# esp32_pico.net
KiCad netlist of a schematic drawn in Altium Designer
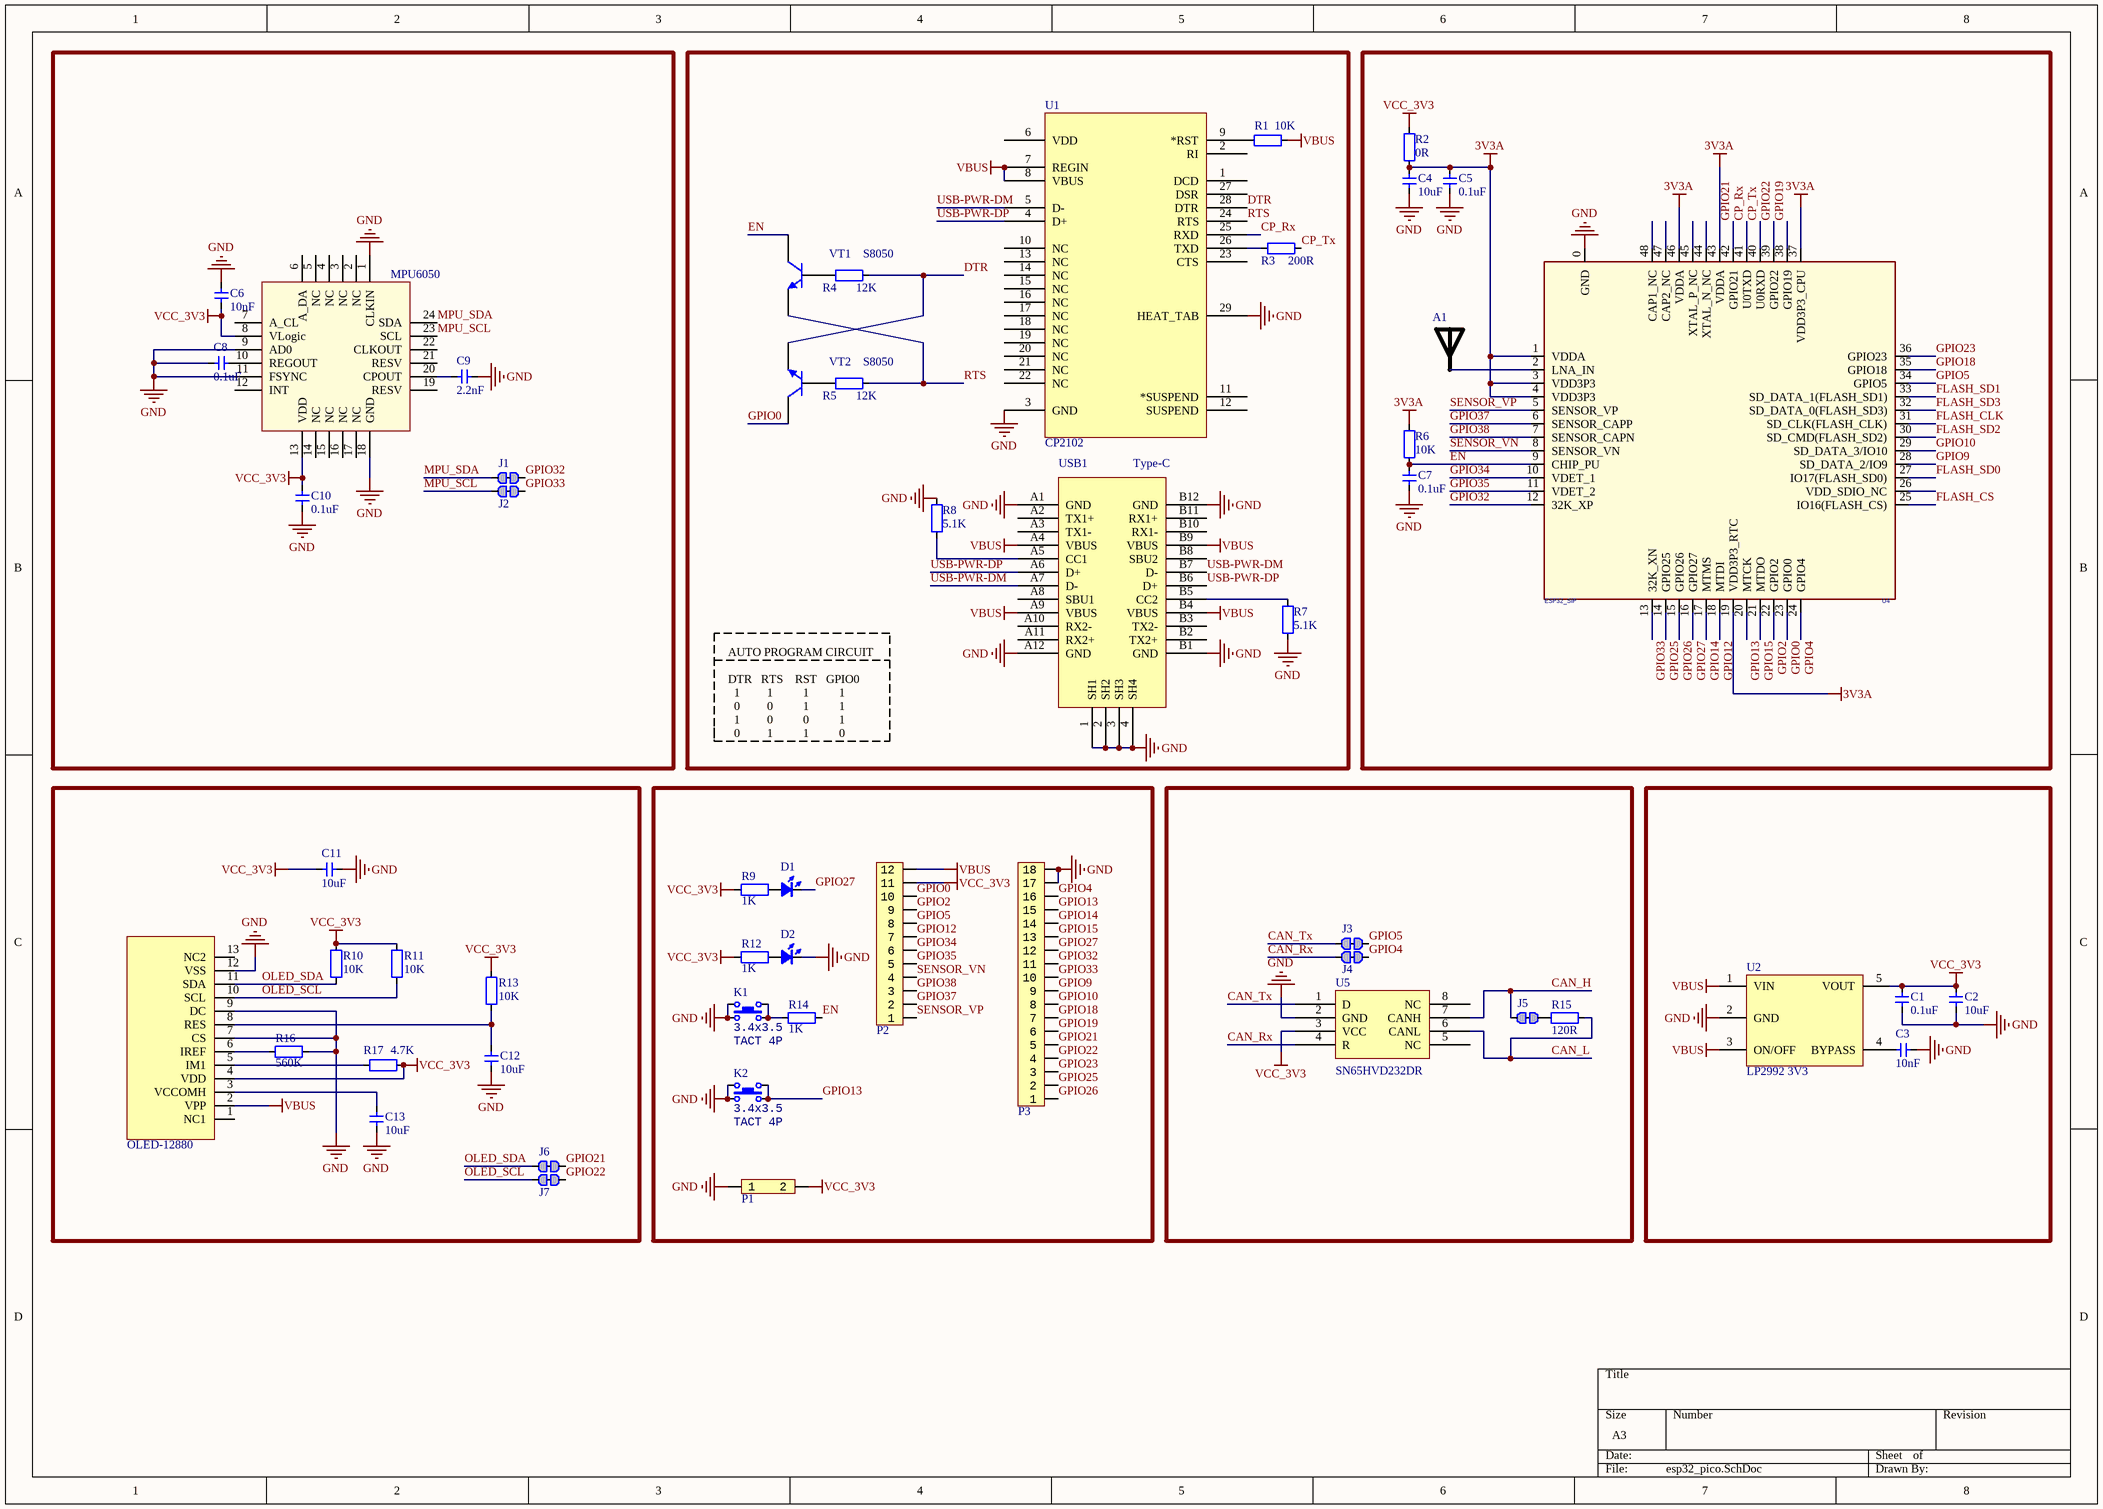
[diagram p0: esp32_pico.SchDoc]

(export (version "E")
  (design (tool "Eeschema 10.0.6"))
  (components
    (comp (ref "1")
      (value "OLED-12880")
      (footprint "OLED-12880")
      (libsource (lib "mLib") (part "OLED-12880"))
    )
    (comp (ref "A1")
      (value "RAINSUN")
      (footprint "ANT-Rainsun-AN5120")
      (libsource (lib "MyPcbLib") (part "ANT-Rainsun-AP5120"))
    )
    (comp (ref "C1")
      (value "0.1uF")
      (footprint "CAP_0402")
      (description "Capacitor")
      (libsource (lib "MyPcbLib") (part "电容-0402"))
    )
    (comp (ref "C2")
      (value "10uF")
      (footprint "CAP_0402")
      (description "Capacitor")
      (libsource (lib "MyPcbLib") (part "电容-0402"))
    )
    (comp (ref "C3")
      (value "10nF")
      (footprint "CAP_0402")
      (description "Capacitor")
      (libsource (lib "MyPcbLib") (part "电容-0402"))
    )
    (comp (ref "C4")
      (value "10uF")
      (footprint "CAP_0402")
      (description "Capacitor")
      (libsource (lib "MyPcbLib") (part "电容-0402"))
    )
    (comp (ref "C5")
      (value "0.1uF")
      (footprint "CAP_0402")
      (description "Capacitor")
      (libsource (lib "MyPcbLib") (part "电容-0402"))
    )
    (comp (ref "C6")
      (value "10nF")
      (footprint "CAP_0402")
      (description "Capacitor")
      (libsource (lib "MyPcbLib") (part "电容-0402"))
    )
    (comp (ref "C7")
      (value "0.1uF")
      (footprint "CAP_0402")
      (description "Capacitor")
      (libsource (lib "MyPcbLib") (part "电容-0402"))
    )
    (comp (ref "C8")
      (value "0.1uF")
      (footprint "CAP_0402")
      (description "Capacitor")
      (libsource (lib "MyPcbLib") (part "电容-0402"))
    )
    (comp (ref "C9")
      (value "2.2nF")
      (footprint "CAP_0402")
      (description "Capacitor")
      (libsource (lib "MyPcbLib") (part "电容-0402"))
    )
    (comp (ref "C10")
      (value "0.1uF")
      (footprint "CAP_0402")
      (description "Capacitor")
      (libsource (lib "MyPcbLib") (part "电容-0402"))
    )
    (comp (ref "C11")
      (value "10uF")
      (footprint "CAP_0402")
      (description "Capacitor")
      (libsource (lib "MyPcbLib") (part "电容-0402"))
    )
    (comp (ref "C12")
      (value "10uF")
      (footprint "CAP_0402")
      (description "Capacitor")
      (libsource (lib "MyPcbLib") (part "电容-0402"))
    )
    (comp (ref "C13")
      (value "10uF")
      (footprint "CAP_0402")
      (description "Capacitor")
      (libsource (lib "MyPcbLib") (part "电容-0402"))
    )
    (comp (ref "D1")
      (value "color?")
      (footprint "LED_0402_RED")
      (description "LED")
      (libsource (lib "KitSprout") (part "LED_0402"))
    )
    (comp (ref "D2")
      (value "color?")
      (footprint "LED_0402_RED")
      (description "LED")
      (libsource (lib "KitSprout") (part "LED_0402"))
    )
    (comp (ref "J1")
      (value "跳线")
      (footprint "0402-0R")
      (description "Resistor")
      (fields (field (name "PUBLISHER") "Altium Limited"))
      (libsource (lib "MyPcbLib") (part "跳线"))
    )
    (comp (ref "J2")
      (value "跳线")
      (footprint "0402-0R")
      (description "Resistor")
      (fields (field (name "PUBLISHER") "Altium Limited"))
      (libsource (lib "MyPcbLib") (part "跳线"))
    )
    (comp (ref "J3")
      (value "跳线")
      (footprint "0402-0R")
      (description "Resistor")
      (fields (field (name "PUBLISHER") "Altium Limited"))
      (libsource (lib "MyPcbLib") (part "跳线"))
    )
    (comp (ref "J4")
      (value "跳线")
      (footprint "0402-0R")
      (description "Resistor")
      (fields (field (name "PUBLISHER") "Altium Limited"))
      (libsource (lib "MyPcbLib") (part "跳线"))
    )
    (comp (ref "J5")
      (value "跳线")
      (footprint "0402-0R")
      (description "Resistor")
      (fields (field (name "PUBLISHER") "Altium Limited"))
      (libsource (lib "MyPcbLib") (part "跳线"))
    )
    (comp (ref "J6")
      (value "跳线")
      (footprint "0402-0R")
      (description "Resistor")
      (fields (field (name "PUBLISHER") "Altium Limited"))
      (libsource (lib "MyPcbLib") (part "跳线"))
    )
    (comp (ref "J7")
      (value "跳线")
      (footprint "0402-0R")
      (description "Resistor")
      (fields (field (name "PUBLISHER") "Altium Limited"))
      (libsource (lib "MyPcbLib") (part "跳线"))
    )
    (comp (ref "K1")
      (value "3.4x3.5")
      (footprint "ButtonTACT_3.5*3.55_90")
      (description "Button")
      (fields (field (name "TYPE") "TACT 4P") (field (name "Comment") "TACT 4P"))
      (libsource (lib "KitSprout") (part "ButtonTACT"))
    )
    (comp (ref "K2")
      (value "3.4x3.5")
      (footprint "ButtonTACT_3.5*3.55_90")
      (description "Button")
      (fields (field (name "TYPE") "TACT 4P") (field (name "Comment") "TACT 4P"))
      (libsource (lib "KitSprout") (part "ButtonTACT"))
    )
    (comp (ref "P1")
      (value "HDR2x1_2.54")
      (footprint "HDR1X2_2.54_180")
      (description "Header")
      (libsource (lib "KitSprout") (part "HDR2x1_2.54"))
    )
    (comp (ref "P2")
      (value "HDR1x12_2.54")
      (footprint "HDR1X12_2.54_180")
      (description "Header")
      (libsource (lib "KitSprout") (part "HDR1x12_2.54"))
    )
    (comp (ref "P3")
      (value "HDR1x18_2.54")
      (footprint "HDR1X18_2.54_180")
      (description "Header")
      (libsource (lib "KitSprout") (part "HDR1x18_2.54"))
    )
    (comp (ref "R1")
      (value "10K")
      (footprint "RES_0402")
      (description "Resistor")
      (libsource (lib "") (part "电阻-0402_3"))
    )
    (comp (ref "R2")
      (value "0R")
      (footprint "RES_0402")
      (description "Resistor")
      (libsource (lib "") (part "电阻-0402_1"))
    )
    (comp (ref "R3")
      (value "200R")
      (footprint "RES_0402")
      (description "Resistor")
      (libsource (lib "") (part "电阻-0402_3"))
    )
    (comp (ref "R4")
      (value "12K")
      (footprint "RES_0402")
      (description "Resistor")
      (libsource (lib "") (part "电阻-0402_3"))
    )
    (comp (ref "R5")
      (value "12K")
      (footprint "RES_0402")
      (description "Resistor")
      (libsource (lib "") (part "电阻-0402_3"))
    )
    (comp (ref "R6")
      (value "10K")
      (footprint "RES_0402")
      (description "Resistor")
      (libsource (lib "") (part "电阻-0402_1"))
    )
    (comp (ref "R7")
      (value "5.1K")
      (footprint "RES_0402")
      (description "Resistor")
      (libsource (lib "") (part "电阻-0402_1"))
    )
    (comp (ref "R8")
      (value "5.1K")
      (footprint "RES_0402")
      (description "Resistor")
      (libsource (lib "") (part "电阻-0402_2"))
    )
    (comp (ref "R9")
      (value "1K")
      (footprint "RES_0402")
      (description "Resistor")
      (libsource (lib "MyPcbLib") (part "电阻-0402"))
    )
    (comp (ref "R10")
      (value "10K")
      (footprint "RES_0402")
      (description "Resistor")
      (libsource (lib "") (part "电阻-0402_2"))
    )
    (comp (ref "R11")
      (value "10K")
      (footprint "RES_0402")
      (description "Resistor")
      (libsource (lib "") (part "电阻-0402_2"))
    )
    (comp (ref "R12")
      (value "1K")
      (footprint "RES_0402")
      (description "Resistor")
      (libsource (lib "MyPcbLib") (part "电阻-0402"))
    )
    (comp (ref "R13")
      (value "10K")
      (footprint "RES_0402")
      (description "Resistor")
      (libsource (lib "") (part "电阻-0402_2"))
    )
    (comp (ref "R14")
      (value "1K")
      (footprint "RES_0402")
      (description "Resistor")
      (libsource (lib "MyPcbLib") (part "电阻-0402"))
    )
    (comp (ref "R15")
      (value "120R")
      (footprint "RES_0402")
      (description "Resistor")
      (libsource (lib "MyPcbLib") (part "电阻-0402"))
    )
    (comp (ref "R16")
      (value "560K")
      (footprint "RES_0402")
      (description "Resistor")
      (libsource (lib "MyPcbLib") (part "电阻-0402"))
    )
    (comp (ref "R17")
      (value "4.7K")
      (footprint "RES_0402")
      (description "Resistor")
      (libsource (lib "MyPcbLib") (part "电阻-0402"))
    )
    (comp (ref "U1")
      (value "CP2102")
      (footprint "QFN-28")
      (description "USB转TTL")
      (libsource (lib "mLib") (part "CP2102"))
    )
    (comp (ref "U2")
      (value "LP2992 3V3")
      (footprint "SOT23-5")
      (description "LDO")
      (libsource (lib "MyPcbLib") (part "LP2992"))
    )
    (comp (ref "U3")
      (value "MPU6050")
      (footprint "QFN-24")
      (description "六轴传感器")
      (libsource (lib "mLib") (part "MPU6050"))
    )
    (comp (ref "U4")
      (value "ESP32_SIP")
      (footprint "QFN-48_7X7")
      (libsource (lib "MyPcbLib") (part "ESP32-PICO"))
    )
    (comp (ref "U5")
      (value "SN65HVD232D")
      (footprint "SO-8")
      (fields
        (field (name "MANUFACTURER") "Texas Instruments")
        (field (name "MANUFACTURER PART NUMBER") "SN65HVD232DR")
      )
      (libsource (lib "MyPcbLib") (part "SN65HVD232D"))
    )
    (comp (ref "USB1")
      (value "Type-C")
      (footprint "Type-C-TOP")
      (libsource (lib "MyPcbLib") (part "USB-Type-C-TOP"))
    )
    (comp (ref "VT1")
      (value "S8050")
      (footprint "SMT_TRIODE_NPN")
      (description "Surface mount NPN transistor, package SOT-23")
      (libsource (lib "MyPcbLib") (part "SMT_TRIODE_NPN"))
    )
    (comp (ref "VT2")
      (value "S8050")
      (footprint "SMT_TRIODE_NPN")
      (description "Surface mount NPN transistor, package SOT-23")
      (libsource (lib "MyPcbLib") (part "SMT_TRIODE_NPN"))
    )
  )
  (nets
    (net (code "1") (name "/CAN_H") (class "Default")
      (node (ref "J5") (pin "1") (pinfunction "1_1") (pintype "passive"))
      (node (ref "U5") (pin "7") (pinfunction "CANH_7") (pintype "passive"))
    )
    (net (code "2") (name "/CAN_L") (class "Default")
      (node (ref "R15") (pin "2") (pinfunction "2_2") (pintype "passive"))
      (node (ref "U5") (pin "6") (pinfunction "CANL_6") (pintype "passive"))
    )
    (net (code "3") (name "/CAN_Rx") (class "Default")
      (node (ref "J4") (pin "1") (pinfunction "1_1") (pintype "passive"))
      (node (ref "U5") (pin "4") (pinfunction "R_4") (pintype "passive"))
    )
    (net (code "4") (name "/CAN_Tx") (class "Default")
      (node (ref "J3") (pin "1") (pinfunction "1_1") (pintype "passive"))
      (node (ref "U5") (pin "1") (pinfunction "D_1") (pintype "passive"))
    )
    (net (code "5") (name "/CP_Rx") (class "Default")
      (node (ref "U1") (pin "25") (pinfunction "RXD_25") (pintype "passive"))
      (node (ref "U4") (pin "41") (pinfunction "U0TXD_41") (pintype "power_in"))
    )
    (net (code "6") (name "/CP_Tx") (class "Default")
      (node (ref "R3") (pin "1") (pinfunction "1_1") (pintype "passive"))
      (node (ref "U4") (pin "40") (pinfunction "U0RXD_40") (pintype "power_in"))
    )
    (net (code "7") (name "/DTR") (class "Default")
      (node (ref "R4") (pin "1") (pinfunction "1_1") (pintype "passive"))
      (node (ref "U1") (pin "28") (pinfunction "DTR_28") (pintype "passive"))
      (node (ref "VT2") (pin "2") (pinfunction "E_2") (pintype "passive"))
    )
    (net (code "8") (name "/EN") (class "Default")
      (node (ref "C7") (pin "1") (pinfunction "1_1") (pintype "passive"))
      (node (ref "R14") (pin "2") (pinfunction "2_2") (pintype "passive"))
      (node (ref "R6") (pin "2") (pinfunction "2_2") (pintype "passive"))
      (node (ref "U4") (pin "9") (pinfunction "CHIP_PU_9") (pintype "passive"))
      (node (ref "VT1") (pin "3") (pinfunction "C_3") (pintype "passive"))
    )
    (net (code "9") (name "/FLASH_CLK") (class "Default")
      (node (ref "U4") (pin "31") (pinfunction "SD_CLK(FLASH_CLK)_31") (pintype "passive"))
    )
    (net (code "10") (name "/FLASH_CS") (class "Default")
      (node (ref "U4") (pin "25") (pinfunction "IO16(FLASH_CS)_25") (pintype "passive"))
    )
    (net (code "11") (name "/FLASH_SD0") (class "Default")
      (node (ref "U4") (pin "27") (pinfunction "IO17(FLASH_SD0)_27") (pintype "passive"))
    )
    (net (code "12") (name "/FLASH_SD1") (class "Default")
      (node (ref "U4") (pin "33") (pinfunction "SD_DATA_1(FLASH_SD1)_33") (pintype "passive"))
    )
    (net (code "13") (name "/FLASH_SD2") (class "Default")
      (node (ref "U4") (pin "30") (pinfunction "SD_CMD(FLASH_SD2)_30") (pintype "passive"))
    )
    (net (code "14") (name "/FLASH_SD3") (class "Default")
      (node (ref "U4") (pin "32") (pinfunction "SD_DATA_0(FLASH_SD3)_32") (pintype "passive"))
    )
    (net (code "15") (name "/GPIO0") (class "Default")
      (node (ref "P2") (pin "10") (pinfunction "10_10") (pintype "passive"))
      (node (ref "U4") (pin "23") (pinfunction "GPIO0_23") (pintype "passive"))
      (node (ref "VT2") (pin "3") (pinfunction "C_3") (pintype "passive"))
    )
    (net (code "16") (name "/GPIO2") (class "Default")
      (node (ref "P2") (pin "9") (pinfunction "9_9") (pintype "passive"))
      (node (ref "U4") (pin "22") (pinfunction "GPIO2_22") (pintype "passive"))
    )
    (net (code "17") (name "/GPIO4") (class "Default")
      (node (ref "J4") (pin "2") (pinfunction "2_2") (pintype "passive"))
      (node (ref "P3") (pin "16") (pinfunction "16_16") (pintype "passive"))
      (node (ref "U4") (pin "24") (pinfunction "GPIO4_24") (pintype "passive"))
    )
    (net (code "18") (name "/GPIO5") (class "Default")
      (node (ref "J3") (pin "2") (pinfunction "2_2") (pintype "passive"))
      (node (ref "P2") (pin "8") (pinfunction "8_8") (pintype "passive"))
      (node (ref "U4") (pin "34") (pinfunction "GPIO5_34") (pintype "passive"))
    )
    (net (code "19") (name "/GPIO9") (class "Default")
      (node (ref "P3") (pin "9") (pinfunction "9_9") (pintype "passive"))
      (node (ref "U4") (pin "28") (pinfunction "SD_DATA_2/IO9_28") (pintype "passive"))
    )
    (net (code "20") (name "/GPIO10") (class "Default")
      (node (ref "P3") (pin "8") (pinfunction "8_8") (pintype "passive"))
      (node (ref "U4") (pin "29") (pinfunction "SD_DATA_3/IO10_29") (pintype "passive"))
    )
    (net (code "21") (name "/GPIO12") (class "Default")
      (node (ref "P2") (pin "7") (pinfunction "7_7") (pintype "passive"))
      (node (ref "U4") (pin "18") (pinfunction "MTDI_18") (pintype "passive"))
    )
    (net (code "22") (name "/GPIO13") (class "Default")
      (node (ref "K2") (pin "2") (pinfunction "2_2") (pintype "passive"))
      (node (ref "K2") (pin "4") (pinfunction "4_4") (pintype "passive"))
      (node (ref "P3") (pin "15") (pinfunction "15_15") (pintype "passive"))
      (node (ref "U4") (pin "20") (pinfunction "MTCK_20") (pintype "passive"))
    )
    (net (code "23") (name "/GPIO14") (class "Default")
      (node (ref "P3") (pin "14") (pinfunction "14_14") (pintype "passive"))
      (node (ref "U4") (pin "17") (pinfunction "MTMS_17") (pintype "passive"))
    )
    (net (code "24") (name "/GPIO15") (class "Default")
      (node (ref "P3") (pin "13") (pinfunction "13_13") (pintype "passive"))
      (node (ref "U4") (pin "21") (pinfunction "MTDO_21") (pintype "passive"))
    )
    (net (code "25") (name "/GPIO18") (class "Default")
      (node (ref "P3") (pin "7") (pinfunction "7_7") (pintype "passive"))
      (node (ref "U4") (pin "35") (pinfunction "GPIO18_35") (pintype "passive"))
    )
    (net (code "26") (name "/GPIO19") (class "Default")
      (node (ref "P3") (pin "6") (pinfunction "6_6") (pintype "passive"))
      (node (ref "U4") (pin "38") (pinfunction "GPIO19_38") (pintype "passive"))
    )
    (net (code "27") (name "/GPIO21") (class "Default")
      (node (ref "J6") (pin "2") (pinfunction "2_2") (pintype "passive"))
      (node (ref "P3") (pin "5") (pinfunction "5_5") (pintype "passive"))
      (node (ref "U4") (pin "42") (pinfunction "GPIO21_42") (pintype "passive"))
    )
    (net (code "28") (name "/GPIO22") (class "Default")
      (node (ref "J7") (pin "2") (pinfunction "2_2") (pintype "passive"))
      (node (ref "P3") (pin "4") (pinfunction "4_4") (pintype "passive"))
      (node (ref "U4") (pin "39") (pinfunction "GPIO22_39") (pintype "passive"))
    )
    (net (code "29") (name "/GPIO23") (class "Default")
      (node (ref "P3") (pin "3") (pinfunction "3_3") (pintype "passive"))
      (node (ref "U4") (pin "36") (pinfunction "GPIO23_36") (pintype "passive"))
    )
    (net (code "30") (name "/GPIO25") (class "Default")
      (node (ref "P3") (pin "2") (pinfunction "2_2") (pintype "passive"))
      (node (ref "U4") (pin "14") (pinfunction "GPIO25_14") (pintype "passive"))
    )
    (net (code "31") (name "/GPIO26") (class "Default")
      (node (ref "P3") (pin "1") (pinfunction "1_1") (pintype "passive"))
      (node (ref "U4") (pin "15") (pinfunction "GPIO26_15") (pintype "passive"))
    )
    (net (code "32") (name "/GPIO27") (class "Default")
      (node (ref "D1") (pin "2") (pinfunction "K_2") (pintype "passive"))
      (node (ref "P3") (pin "12") (pinfunction "12_12") (pintype "passive"))
      (node (ref "U4") (pin "16") (pinfunction "GPIO27_16") (pintype "passive"))
    )
    (net (code "33") (name "/GPIO32") (class "Default")
      (node (ref "J1") (pin "2") (pinfunction "2_2") (pintype "passive"))
      (node (ref "P3") (pin "11") (pinfunction "11_11") (pintype "passive"))
      (node (ref "U4") (pin "12") (pinfunction "32K_XP_12") (pintype "passive"))
    )
    (net (code "34") (name "/GPIO33") (class "Default")
      (node (ref "J2") (pin "2") (pinfunction "2_2") (pintype "passive"))
      (node (ref "P3") (pin "10") (pinfunction "10_10") (pintype "passive"))
      (node (ref "U4") (pin "13") (pinfunction "32K_XN_13") (pintype "passive"))
    )
    (net (code "35") (name "/GPIO34") (class "Default")
      (node (ref "P2") (pin "6") (pinfunction "6_6") (pintype "passive"))
      (node (ref "U4") (pin "10") (pinfunction "VDET_1_10") (pintype "passive"))
    )
    (net (code "36") (name "/GPIO35") (class "Default")
      (node (ref "P2") (pin "5") (pinfunction "5_5") (pintype "passive"))
      (node (ref "U4") (pin "11") (pinfunction "VDET_2_11") (pintype "passive"))
    )
    (net (code "37") (name "/GPIO37") (class "Default")
      (node (ref "P2") (pin "2") (pinfunction "2_2") (pintype "passive"))
      (node (ref "U4") (pin "6") (pinfunction "SENSOR_CAPP_6") (pintype "passive"))
    )
    (net (code "38") (name "/GPIO38") (class "Default")
      (node (ref "P2") (pin "3") (pinfunction "3_3") (pintype "passive"))
      (node (ref "U4") (pin "7") (pinfunction "SENSOR_CAPN_7") (pintype "passive"))
    )
    (net (code "39") (name "/MPU_SCL") (class "Default")
      (node (ref "J2") (pin "1") (pinfunction "1_1") (pintype "passive"))
      (node (ref "U3") (pin "23") (pinfunction "SCL_23") (pintype "passive"))
    )
    (net (code "40") (name "/MPU_SDA") (class "Default")
      (node (ref "J1") (pin "1") (pinfunction "1_1") (pintype "passive"))
      (node (ref "U3") (pin "24") (pinfunction "SDA_24") (pintype "passive"))
    )
    (net (code "41") (name "/OLED_SCL") (class "Default")
      (node (ref "1") (pin "10") (pinfunction "SCL_10") (pintype "passive"))
      (node (ref "J7") (pin "1") (pinfunction "1_1") (pintype "passive"))
      (node (ref "R11") (pin "1") (pinfunction "1_1") (pintype "passive"))
    )
    (net (code "42") (name "/OLED_SDA") (class "Default")
      (node (ref "1") (pin "11") (pinfunction "SDA_11") (pintype "passive"))
      (node (ref "J6") (pin "1") (pinfunction "1_1") (pintype "passive"))
      (node (ref "R10") (pin "1") (pinfunction "1_1") (pintype "passive"))
    )
    (net (code "43") (name "/RTS") (class "Default")
      (node (ref "R5") (pin "1") (pinfunction "1_1") (pintype "passive"))
      (node (ref "U1") (pin "24") (pinfunction "RTS_24") (pintype "passive"))
      (node (ref "VT1") (pin "2") (pinfunction "E_2") (pintype "passive"))
    )
    (net (code "44") (name "/SENSOR_VN") (class "Default")
      (node (ref "P2") (pin "4") (pinfunction "4_4") (pintype "passive"))
      (node (ref "U4") (pin "8") (pinfunction "SENSOR_VN_8") (pintype "passive"))
    )
    (net (code "45") (name "/SENSOR_VP") (class "Default")
      (node (ref "P2") (pin "1") (pinfunction "1_1") (pintype "passive"))
      (node (ref "U4") (pin "5") (pinfunction "SENSOR_VP_5") (pintype "passive"))
    )
    (net (code "46") (name "/USB-PWR-DM") (class "Default")
      (node (ref "U1") (pin "5") (pinfunction "D-_5") (pintype "passive"))
      (node (ref "USB1") (pin "A7") (pinfunction "D-_A7") (pintype "passive"))
      (node (ref "USB1") (pin "B7") (pinfunction "D-_B7") (pintype "passive"))
    )
    (net (code "47") (name "/USB-PWR-DP") (class "Default")
      (node (ref "U1") (pin "4") (pinfunction "D+_4") (pintype "passive"))
      (node (ref "USB1") (pin "A6") (pinfunction "D+_A6") (pintype "passive"))
      (node (ref "USB1") (pin "B6") (pinfunction "D+_B6") (pintype "passive"))
    )
    (net (code "48") (name "3V3A") (class "Default")
      (node (ref "C4") (pin "2") (pinfunction "2_2") (pintype "passive"))
      (node (ref "C5") (pin "2") (pinfunction "2_2") (pintype "passive"))
      (node (ref "R2") (pin "2") (pinfunction "2_2") (pintype "passive"))
      (node (ref "R6") (pin "1") (pinfunction "1_1") (pintype "passive"))
      (node (ref "U4") (pin "1") (pinfunction "VDDA_1") (pintype "power_in"))
      (node (ref "U4") (pin "19") (pinfunction "VDD3P3_RTC_19") (pintype "power_in"))
      (node (ref "U4") (pin "3") (pinfunction "VDD3P3_3") (pintype "power_in"))
      (node (ref "U4") (pin "37") (pinfunction "VDD3P3_CPU_37") (pintype "power_in"))
      (node (ref "U4") (pin "4") (pinfunction "VDD3P3_4") (pintype "power_in"))
      (node (ref "U4") (pin "43") (pinfunction "VDDA_43") (pintype "power_in"))
      (node (ref "U4") (pin "46") (pinfunction "VDDA_46") (pintype "power_in"))
    )
    (net (code "49") (name "GND") (class "Default")
      (node (ref "1") (pin "12") (pinfunction "VSS_12") (pintype "passive"))
      (node (ref "1") (pin "7") (pinfunction "CS_7") (pintype "passive"))
      (node (ref "1") (pin "9") (pinfunction "DC_9") (pintype "passive"))
      (node (ref "C1") (pin "1") (pinfunction "1_1") (pintype "passive"))
      (node (ref "C10") (pin "1") (pinfunction "1_1") (pintype "passive"))
      (node (ref "C11") (pin "1") (pinfunction "1_1") (pintype "passive"))
      (node (ref "C12") (pin "1") (pinfunction "1_1") (pintype "passive"))
      (node (ref "C13") (pin "1") (pinfunction "1_1") (pintype "passive"))
      (node (ref "C2") (pin "1") (pinfunction "1_1") (pintype "passive"))
      (node (ref "C3") (pin "1") (pinfunction "1_1") (pintype "passive"))
      (node (ref "C4") (pin "1") (pinfunction "1_1") (pintype "passive"))
      (node (ref "C5") (pin "1") (pinfunction "1_1") (pintype "passive"))
      (node (ref "C6") (pin "2") (pinfunction "2_2") (pintype "passive"))
      (node (ref "C7") (pin "2") (pinfunction "2_2") (pintype "passive"))
      (node (ref "C8") (pin "2") (pinfunction "2_2") (pintype "passive"))
      (node (ref "C9") (pin "1") (pinfunction "1_1") (pintype "passive"))
      (node (ref "D2") (pin "2") (pinfunction "K_2") (pintype "passive"))
      (node (ref "K1") (pin "1") (pinfunction "1_1") (pintype "passive"))
      (node (ref "K1") (pin "3") (pinfunction "3_3") (pintype "passive"))
      (node (ref "K2") (pin "1") (pinfunction "1_1") (pintype "passive"))
      (node (ref "K2") (pin "3") (pinfunction "3_3") (pintype "passive"))
      (node (ref "P1") (pin "1") (pinfunction "1_1") (pintype "passive"))
      (node (ref "P3") (pin "17") (pinfunction "17_17") (pintype "passive"))
      (node (ref "P3") (pin "18") (pinfunction "18_18") (pintype "passive"))
      (node (ref "R16") (pin "2") (pinfunction "2_2") (pintype "passive"))
      (node (ref "R7") (pin "2") (pinfunction "2_2") (pintype "passive"))
      (node (ref "R8") (pin "2") (pinfunction "2_2") (pintype "passive"))
      (node (ref "U1") (pin "29") (pinfunction "HEAT_TAB_29") (pintype "passive"))
      (node (ref "U1") (pin "3") (pinfunction "GND_3") (pintype "passive"))
      (node (ref "U2") (pin "2") (pinfunction "GND_2") (pintype "passive"))
      (node (ref "U3") (pin "1") (pinfunction "CLKIN_1") (pintype "passive"))
      (node (ref "U3") (pin "11") (pinfunction "FSYNC_11") (pintype "passive"))
      (node (ref "U3") (pin "18") (pinfunction "GND_18") (pintype "passive"))
      (node (ref "U3") (pin "9") (pinfunction "AD0_9") (pintype "passive"))
      (node (ref "U4") (pin "0") (pinfunction "GND_0") (pintype "power_in"))
      (node (ref "U5") (pin "2") (pinfunction "GND_2") (pintype "passive"))
      (node (ref "USB1") (pin "1") (pinfunction "SH1_1") (pintype "passive"))
      (node (ref "USB1") (pin "2") (pinfunction "SH2_2") (pintype "passive"))
      (node (ref "USB1") (pin "3") (pinfunction "SH3_3") (pintype "passive"))
      (node (ref "USB1") (pin "4") (pinfunction "SH4_4") (pintype "passive"))
      (node (ref "USB1") (pin "A1") (pinfunction "GND_A1") (pintype "passive"))
      (node (ref "USB1") (pin "A12") (pinfunction "GND_A12") (pintype "passive"))
      (node (ref "USB1") (pin "B1") (pinfunction "GND_B1") (pintype "passive"))
      (node (ref "USB1") (pin "B12") (pinfunction "GND_B12") (pintype "passive"))
    )
    (net (code "50") (name "Net-(1-IM1)") (class "Default")
      (node (ref "1") (pin "5") (pinfunction "IM1_5") (pintype "passive"))
      (node (ref "R17") (pin "1") (pinfunction "1_1") (pintype "passive"))
    )
    (net (code "51") (name "Net-(1-IREF)") (class "Default")
      (node (ref "1") (pin "6") (pinfunction "IREF_6") (pintype "passive"))
      (node (ref "R16") (pin "1") (pinfunction "1_1") (pintype "passive"))
    )
    (net (code "52") (name "Net-(1-RES)") (class "Default")
      (node (ref "1") (pin "8") (pinfunction "RES_8") (pintype "passive"))
      (node (ref "C12") (pin "2") (pinfunction "2_2") (pintype "passive"))
      (node (ref "R13") (pin "1") (pinfunction "1_1") (pintype "passive"))
    )
    (net (code "53") (name "Net-(1-VCCOMH)") (class "Default")
      (node (ref "1") (pin "3") (pinfunction "VCCOMH_3") (pintype "passive"))
      (node (ref "C13") (pin "2") (pinfunction "2_2") (pintype "passive"))
    )
    (net (code "54") (name "Net-(D1-A)") (class "Default")
      (node (ref "D1") (pin "1") (pinfunction "A_1") (pintype "passive"))
      (node (ref "R9") (pin "2") (pinfunction "2_2") (pintype "passive"))
    )
    (net (code "55") (name "Net-(D2-A)") (class "Default")
      (node (ref "D2") (pin "1") (pinfunction "A_1") (pintype "passive"))
      (node (ref "R12") (pin "2") (pinfunction "2_2") (pintype "passive"))
    )
    (net (code "56") (name "Net-(J5-Pad2)") (class "Default")
      (node (ref "J5") (pin "2") (pinfunction "2_2") (pintype "passive"))
      (node (ref "R15") (pin "1") (pinfunction "1_1") (pintype "passive"))
    )
    (net (code "57") (name "Net-(K1-Pad2)") (class "Default")
      (node (ref "K1") (pin "2") (pinfunction "2_2") (pintype "passive"))
      (node (ref "K1") (pin "4") (pinfunction "4_4") (pintype "passive"))
      (node (ref "R14") (pin "1") (pinfunction "1_1") (pintype "passive"))
    )
    (net (code "58") (name "Net-(U1-*RST)") (class "Default")
      (node (ref "R1") (pin "2") (pinfunction "2_2") (pintype "passive"))
      (node (ref "U1") (pin "9") (pinfunction "*RST_9") (pintype "passive"))
    )
    (net (code "59") (name "Net-(U1-TXD)") (class "Default")
      (node (ref "R3") (pin "2") (pinfunction "2_2") (pintype "passive"))
      (node (ref "U1") (pin "26") (pinfunction "TXD_26") (pintype "passive"))
    )
    (net (code "60") (name "Net-(U2-BYPASS)") (class "Default")
      (node (ref "C3") (pin "2") (pinfunction "2_2") (pintype "passive"))
      (node (ref "U2") (pin "4") (pinfunction "BYPASS_4") (pintype "passive"))
    )
    (net (code "61") (name "Net-(U3-CPOUT)") (class "Default")
      (node (ref "C9") (pin "2") (pinfunction "2_2") (pintype "passive"))
      (node (ref "U3") (pin "20") (pinfunction "CPOUT_20") (pintype "passive"))
    )
    (net (code "62") (name "Net-(U3-REGOUT)") (class "Default")
      (node (ref "C8") (pin "1") (pinfunction "1_1") (pintype "passive"))
      (node (ref "U3") (pin "10") (pinfunction "REGOUT_10") (pintype "passive"))
    )
    (net (code "63") (name "Net-(U4-LNA_IN)") (class "Default")
      (node (ref "A1") (pin "1") (pinfunction "1_1") (pintype "passive"))
      (node (ref "U4") (pin "2") (pinfunction "LNA_IN_2") (pintype "passive"))
    )
    (net (code "64") (name "Net-(USB1-CC1)") (class "Default")
      (node (ref "R8") (pin "1") (pinfunction "1_1") (pintype "passive"))
      (node (ref "USB1") (pin "A5") (pinfunction "CC1_A5") (pintype "passive"))
    )
    (net (code "65") (name "Net-(USB1-CC2)") (class "Default")
      (node (ref "R7") (pin "1") (pinfunction "1_1") (pintype "passive"))
      (node (ref "USB1") (pin "B5") (pinfunction "CC2_B5") (pintype "passive"))
    )
    (net (code "66") (name "Net-(VT1-B)") (class "Default")
      (node (ref "R4") (pin "2") (pinfunction "2_2") (pintype "passive"))
      (node (ref "VT1") (pin "1") (pinfunction "B_1") (pintype "passive"))
    )
    (net (code "67") (name "Net-(VT2-B)") (class "Default")
      (node (ref "R5") (pin "2") (pinfunction "2_2") (pintype "passive"))
      (node (ref "VT2") (pin "1") (pinfunction "B_1") (pintype "passive"))
    )
    (net (code "68") (name "VBUS") (class "Default")
      (node (ref "1") (pin "2") (pinfunction "VPP_2") (pintype "passive"))
      (node (ref "P2") (pin "12") (pinfunction "12_12") (pintype "passive"))
      (node (ref "R1") (pin "1") (pinfunction "1_1") (pintype "passive"))
      (node (ref "U1") (pin "7") (pinfunction "REGIN_7") (pintype "passive"))
      (node (ref "U1") (pin "8") (pinfunction "VBUS_8") (pintype "passive"))
      (node (ref "U2") (pin "1") (pinfunction "VIN_1") (pintype "passive"))
      (node (ref "U2") (pin "3") (pinfunction "ON/OFF_3") (pintype "passive"))
      (node (ref "USB1") (pin "A4") (pinfunction "VBUS_A4") (pintype "passive"))
      (node (ref "USB1") (pin "A9") (pinfunction "VBUS_A9") (pintype "passive"))
      (node (ref "USB1") (pin "B4") (pinfunction "VBUS_B4") (pintype "passive"))
      (node (ref "USB1") (pin "B9") (pinfunction "VBUS_B9") (pintype "passive"))
    )
    (net (code "69") (name "VCC_3V3") (class "Default")
      (node (ref "1") (pin "4") (pinfunction "VDD_4") (pintype "passive"))
      (node (ref "C1") (pin "2") (pinfunction "2_2") (pintype "passive"))
      (node (ref "C10") (pin "2") (pinfunction "2_2") (pintype "passive"))
      (node (ref "C11") (pin "2") (pinfunction "2_2") (pintype "passive"))
      (node (ref "C2") (pin "2") (pinfunction "2_2") (pintype "passive"))
      (node (ref "C6") (pin "1") (pinfunction "1_1") (pintype "passive"))
      (node (ref "P1") (pin "2") (pinfunction "2_2") (pintype "passive"))
      (node (ref "P2") (pin "11") (pinfunction "11_11") (pintype "passive"))
      (node (ref "R10") (pin "2") (pinfunction "2_2") (pintype "passive"))
      (node (ref "R11") (pin "2") (pinfunction "2_2") (pintype "passive"))
      (node (ref "R12") (pin "1") (pinfunction "1_1") (pintype "passive"))
      (node (ref "R13") (pin "2") (pinfunction "2_2") (pintype "passive"))
      (node (ref "R17") (pin "2") (pinfunction "2_2") (pintype "passive"))
      (node (ref "R2") (pin "1") (pinfunction "1_1") (pintype "passive"))
      (node (ref "R9") (pin "1") (pinfunction "1_1") (pintype "passive"))
      (node (ref "U2") (pin "5") (pinfunction "VOUT_5") (pintype "passive"))
      (node (ref "U3") (pin "13") (pinfunction "VDD_13") (pintype "passive"))
      (node (ref "U3") (pin "8") (pinfunction "VLogic_8") (pintype "passive"))
      (node (ref "U5") (pin "3") (pinfunction "VCC_3") (pintype "passive"))
    )
    (net (code "70") (name "unconnected-(1-NC1-Pad1)") (class "Default")
      (node (ref "1") (pin "1") (pinfunction "NC1_1") (pintype "passive"))
    )
    (net (code "71") (name "unconnected-(1-NC2-Pad13)") (class "Default")
      (node (ref "1") (pin "13") (pinfunction "NC2_13") (pintype "passive"))
    )
    (net (code "72") (name "unconnected-(U1-*SUSPEND-Pad11)") (class "Default")
      (node (ref "U1") (pin "11") (pinfunction "*SUSPEND_11") (pintype "passive"))
    )
    (net (code "73") (name "unconnected-(U1-CTS-Pad23)") (class "Default")
      (node (ref "U1") (pin "23") (pinfunction "CTS_23") (pintype "passive"))
    )
    (net (code "74") (name "unconnected-(U1-DCD-Pad1)") (class "Default")
      (node (ref "U1") (pin "1") (pinfunction "DCD_1") (pintype "passive"))
    )
    (net (code "75") (name "unconnected-(U1-DSR-Pad27)") (class "Default")
      (node (ref "U1") (pin "27") (pinfunction "DSR_27") (pintype "passive"))
    )
    (net (code "76") (name "unconnected-(U1-NC-Pad10)") (class "Default")
      (node (ref "U1") (pin "10") (pinfunction "NC_10") (pintype "passive"))
    )
    (net (code "77") (name "unconnected-(U1-NC-Pad13)") (class "Default")
      (node (ref "U1") (pin "13") (pinfunction "NC_13") (pintype "passive"))
    )
    (net (code "78") (name "unconnected-(U1-NC-Pad14)") (class "Default")
      (node (ref "U1") (pin "14") (pinfunction "NC_14") (pintype "passive"))
    )
    (net (code "79") (name "unconnected-(U1-NC-Pad15)") (class "Default")
      (node (ref "U1") (pin "15") (pinfunction "NC_15") (pintype "passive"))
    )
    (net (code "80") (name "unconnected-(U1-NC-Pad16)") (class "Default")
      (node (ref "U1") (pin "16") (pinfunction "NC_16") (pintype "passive"))
    )
    (net (code "81") (name "unconnected-(U1-NC-Pad17)") (class "Default")
      (node (ref "U1") (pin "17") (pinfunction "NC_17") (pintype "passive"))
    )
    (net (code "82") (name "unconnected-(U1-NC-Pad18)") (class "Default")
      (node (ref "U1") (pin "18") (pinfunction "NC_18") (pintype "passive"))
    )
    (net (code "83") (name "unconnected-(U1-NC-Pad19)") (class "Default")
      (node (ref "U1") (pin "19") (pinfunction "NC_19") (pintype "passive"))
    )
    (net (code "84") (name "unconnected-(U1-NC-Pad20)") (class "Default")
      (node (ref "U1") (pin "20") (pinfunction "NC_20") (pintype "passive"))
    )
    (net (code "85") (name "unconnected-(U1-NC-Pad21)") (class "Default")
      (node (ref "U1") (pin "21") (pinfunction "NC_21") (pintype "passive"))
    )
    (net (code "86") (name "unconnected-(U1-NC-Pad22)") (class "Default")
      (node (ref "U1") (pin "22") (pinfunction "NC_22") (pintype "passive"))
    )
    (net (code "87") (name "unconnected-(U1-RI-Pad2)") (class "Default")
      (node (ref "U1") (pin "2") (pinfunction "RI_2") (pintype "passive"))
    )
    (net (code "88") (name "unconnected-(U1-SUSPEND-Pad12)") (class "Default")
      (node (ref "U1") (pin "12") (pinfunction "SUSPEND_12") (pintype "passive"))
    )
    (net (code "89") (name "unconnected-(U1-VDD-Pad6)") (class "Default")
      (node (ref "U1") (pin "6") (pinfunction "VDD_6") (pintype "passive"))
    )
    (net (code "90") (name "unconnected-(U3-A_CL-Pad7)") (class "Default")
      (node (ref "U3") (pin "7") (pinfunction "A_CL_7") (pintype "passive"))
    )
    (net (code "91") (name "unconnected-(U3-A_DA-Pad6)") (class "Default")
      (node (ref "U3") (pin "6") (pinfunction "A_DA_6") (pintype "passive"))
    )
    (net (code "92") (name "unconnected-(U3-CLKOUT-Pad22)") (class "Default")
      (node (ref "U3") (pin "22") (pinfunction "CLKOUT_22") (pintype "passive"))
    )
    (net (code "93") (name "unconnected-(U3-INT-Pad12)") (class "Default")
      (node (ref "U3") (pin "12") (pinfunction "INT_12") (pintype "passive"))
    )
    (net (code "94") (name "unconnected-(U3-NC-Pad2)") (class "Default")
      (node (ref "U3") (pin "2") (pinfunction "NC_2") (pintype "passive"))
    )
    (net (code "95") (name "unconnected-(U3-NC-Pad3)") (class "Default")
      (node (ref "U3") (pin "3") (pinfunction "NC_3") (pintype "passive"))
    )
    (net (code "96") (name "unconnected-(U3-NC-Pad4)") (class "Default")
      (node (ref "U3") (pin "4") (pinfunction "NC_4") (pintype "passive"))
    )
    (net (code "97") (name "unconnected-(U3-NC-Pad5)") (class "Default")
      (node (ref "U3") (pin "5") (pinfunction "NC_5") (pintype "passive"))
    )
    (net (code "98") (name "unconnected-(U3-NC-Pad14)") (class "Default")
      (node (ref "U3") (pin "14") (pinfunction "NC_14") (pintype "passive"))
    )
    (net (code "99") (name "unconnected-(U3-NC-Pad15)") (class "Default")
      (node (ref "U3") (pin "15") (pinfunction "NC_15") (pintype "passive"))
    )
    (net (code "100") (name "unconnected-(U3-NC-Pad16)") (class "Default")
      (node (ref "U3") (pin "16") (pinfunction "NC_16") (pintype "passive"))
    )
    (net (code "101") (name "unconnected-(U3-NC-Pad17)") (class "Default")
      (node (ref "U3") (pin "17") (pinfunction "NC_17") (pintype "passive"))
    )
    (net (code "102") (name "unconnected-(U3-RESV-Pad19)") (class "Default")
      (node (ref "U3") (pin "19") (pinfunction "RESV_19") (pintype "passive"))
    )
    (net (code "103") (name "unconnected-(U3-RESV-Pad21)") (class "Default")
      (node (ref "U3") (pin "21") (pinfunction "RESV_21") (pintype "passive"))
    )
    (net (code "104") (name "unconnected-(U4-CAP1_NC-Pad48)") (class "Default")
      (node (ref "U4") (pin "48") (pinfunction "CAP1_NC_48") (pintype "passive"))
    )
    (net (code "105") (name "unconnected-(U4-CAP2_NC-Pad47)") (class "Default")
      (node (ref "U4") (pin "47") (pinfunction "CAP2_NC_47") (pintype "passive"))
    )
    (net (code "106") (name "unconnected-(U4-VDD_SDIO_NC-Pad26)") (class "Default")
      (node (ref "U4") (pin "26") (pinfunction "VDD_SDIO_NC_26") (pintype "passive"))
    )
    (net (code "107") (name "unconnected-(U4-XTAL_N_NC-Pad44)") (class "Default")
      (node (ref "U4") (pin "44") (pinfunction "XTAL_N_NC_44") (pintype "passive"))
    )
    (net (code "108") (name "unconnected-(U4-XTAL_P_NC-Pad45)") (class "Default")
      (node (ref "U4") (pin "45") (pinfunction "XTAL_P_NC_45") (pintype "passive"))
    )
    (net (code "109") (name "unconnected-(U5-NC-Pad5)") (class "Default")
      (node (ref "U5") (pin "5") (pinfunction "NC_5") (pintype "passive"))
    )
    (net (code "110") (name "unconnected-(U5-NC-Pad8)") (class "Default")
      (node (ref "U5") (pin "8") (pinfunction "NC_8") (pintype "passive"))
    )
    (net (code "111") (name "unconnected-(USB1-RX1+-PadB11)") (class "Default")
      (node (ref "USB1") (pin "B11") (pinfunction "RX1+_B11") (pintype "passive"))
    )
    (net (code "112") (name "unconnected-(USB1-RX1--PadB10)") (class "Default")
      (node (ref "USB1") (pin "B10") (pinfunction "RX1-_B10") (pintype "passive"))
    )
    (net (code "113") (name "unconnected-(USB1-RX2+-PadA11)") (class "Default")
      (node (ref "USB1") (pin "A11") (pinfunction "RX2+_A11") (pintype "passive"))
    )
    (net (code "114") (name "unconnected-(USB1-RX2--PadA10)") (class "Default")
      (node (ref "USB1") (pin "A10") (pinfunction "RX2-_A10") (pintype "passive"))
    )
    (net (code "115") (name "unconnected-(USB1-SBU1-PadA8)") (class "Default")
      (node (ref "USB1") (pin "A8") (pinfunction "SBU1_A8") (pintype "passive"))
    )
    (net (code "116") (name "unconnected-(USB1-SBU2-PadB8)") (class "Default")
      (node (ref "USB1") (pin "B8") (pinfunction "SBU2_B8") (pintype "passive"))
    )
    (net (code "117") (name "unconnected-(USB1-TX1+-PadA2)") (class "Default")
      (node (ref "USB1") (pin "A2") (pinfunction "TX1+_A2") (pintype "passive"))
    )
    (net (code "118") (name "unconnected-(USB1-TX1--PadA3)") (class "Default")
      (node (ref "USB1") (pin "A3") (pinfunction "TX1-_A3") (pintype "passive"))
    )
    (net (code "119") (name "unconnected-(USB1-TX2+-PadB2)") (class "Default")
      (node (ref "USB1") (pin "B2") (pinfunction "TX2+_B2") (pintype "passive"))
    )
    (net (code "120") (name "unconnected-(USB1-TX2--PadB3)") (class "Default")
      (node (ref "USB1") (pin "B3") (pinfunction "TX2-_B3") (pintype "passive"))
    )
  )
)
